# Supply_433Mhz.net
KiCad netlist of a schematic drawn in EAGLE
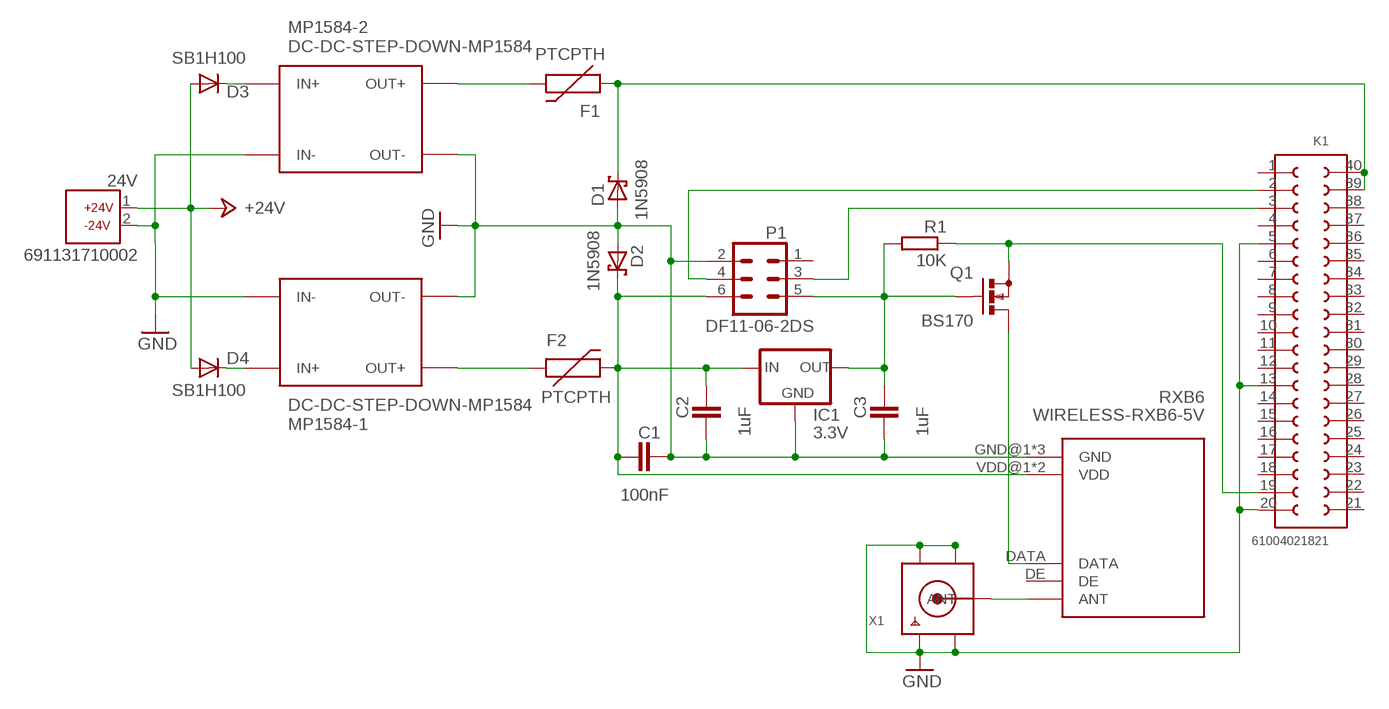
[diagram p0: schematic, sheet 1]

(export (version "E")
  (design (tool "Eeschema 10.0.6"))
  (components
    (comp (ref "24V")
      (value "691131710002")
      (footprint "eagle-import:691131710002")
      (libsource (lib "eagle-import") (part "691131710002"))
    )
    (comp (ref "C1")
      (value "100nF")
      (footprint "eagle-import:C2.5-3")
      (libsource (lib "eagle-import") (part "C2,5-3"))
    )
    (comp (ref "C2")
      (value "1uF")
      (footprint "eagle-import:C5B3")
      (libsource (lib "eagle-import") (part "C5/3"))
    )
    (comp (ref "C3")
      (value "1uF")
      (footprint "eagle-import:C5B3")
      (libsource (lib "eagle-import") (part "C5/3"))
    )
    (comp (ref "D1")
      (value "1N5908")
      (footprint "eagle-import:C4111-15")
      (libsource (lib "eagle-import") (part "1N5908"))
    )
    (comp (ref "D2")
      (value "1N5908")
      (footprint "eagle-import:C4111-15")
      (libsource (lib "eagle-import") (part "1N5908"))
    )
    (comp (ref "D3")
      (value "SB1H100")
      (footprint "eagle-import:DO41-7.6")
      (libsource (lib "eagle-import") (part "DIODE-DO41-7.6"))
    )
    (comp (ref "D4")
      (value "SB1H100")
      (footprint "eagle-import:DO41-7.6")
      (libsource (lib "eagle-import") (part "DIODE-DO41-7.6"))
    )
    (comp (ref "F1")
      (value "PTCPTH")
      (footprint "eagle-import:PTC")
      (libsource (lib "eagle-import") (part "PTCPTH"))
    )
    (comp (ref "F2")
      (value "PTCPTH")
      (footprint "eagle-import:PTC")
      (libsource (lib "eagle-import") (part "PTCPTH"))
    )
    (comp (ref "IC1")
      (value "3.3V")
      (footprint "eagle-import:TO92-INLINE")
      (libsource (lib "eagle-import") (part "MCP1700INLINE"))
    )
    (comp (ref "K1")
      (value "61004021821")
      (footprint "eagle-import:61004021821")
      (libsource (lib "eagle-import") (part "61004021821"))
    )
    (comp (ref "MP1584-1")
      (value "DC-DC-STEP-DOWN-MP1584")
      (footprint "eagle-import:DC-DC-STEP-DOWN-MP1584")
      (libsource (lib "eagle-import") (part "DC-DC-STEP-DOWN-MP1584"))
    )
    (comp (ref "MP1584-2")
      (value "DC-DC-STEP-DOWN-MP1584")
      (footprint "eagle-import:DC-DC-STEP-DOWN-MP1584")
      (libsource (lib "eagle-import") (part "DC-DC-STEP-DOWN-MP1584"))
    )
    (comp (ref "P1")
      (value "DF11-06-2DS")
      (footprint "eagle-import:DF11-06DP-2DS")
      (libsource (lib "eagle-import") (part "DF11-06-2DS"))
    )
    (comp (ref "Q1")
      (value "BS170")
      (footprint "eagle-import:SOT54E")
      (fields (field (name "MF") "ON SEMICONDUCTOR") (field (name "MPN") "BS170G"))
      (libsource (lib "eagle-import") (part "BS170"))
    )
    (comp (ref "R1")
      (value "10K")
      (footprint "eagle-import:0204V")
      (libsource (lib "eagle-import") (part "R-EU_0204/2V"))
    )
    (comp (ref "RXB6")
      (value "WIRELESS-RXB6-5V")
      (footprint "eagle-import:WIRELESS-RXB6-5V")
      (libsource (lib "eagle-import") (part "WIRELESS-RXB6-5V"))
    )
    (comp (ref "X1")
      (value "SMACONNECTOR")
      (footprint "eagle-import:SMA90_DIP")
      (libsource (lib "eagle-import") (part "SMACONNECTOR"))
    )
  )
  (nets
    (net (code "1") (name "+24V") (class "Default")
      (node (ref "24V") (pin "1") (pinfunction "1_1") (pintype "passive"))
      (node (ref "D3") (pin "A") (pinfunction "A_A") (pintype "passive"))
      (node (ref "D4") (pin "A") (pinfunction "A_A") (pintype "passive"))
    )
    (net (code "2") (name "GND") (class "Default")
      (node (ref "24V") (pin "2") (pinfunction "2_2") (pintype "passive"))
      (node (ref "C1") (pin "1") (pinfunction "1_1") (pintype "passive"))
      (node (ref "C2") (pin "2") (pinfunction "2_2") (pintype "passive"))
      (node (ref "C3") (pin "2") (pinfunction "2_2") (pintype "passive"))
      (node (ref "D1") (pin "A") (pinfunction "A_A") (pintype "passive"))
      (node (ref "D2") (pin "A") (pinfunction "A_A") (pintype "passive"))
      (node (ref "IC1") (pin "1") (pinfunction "GND_1") (pintype "input"))
      (node (ref "K1") (pin "13") (pinfunction "13_13") (pintype "passive"))
      (node (ref "K1") (pin "20") (pinfunction "20_20") (pintype "passive"))
      (node (ref "K1") (pin "5") (pinfunction "5_5") (pintype "passive"))
      (node (ref "MP1584-1") (pin "IN-0") (pinfunction "IN-_IN-0") (pintype "bidirectional"))
      (node (ref "MP1584-1") (pin "IN-1") (pinfunction "IN-_IN-1") (pintype "bidirectional"))
      (node (ref "MP1584-1") (pin "OUT-0") (pinfunction "OUT-_OUT-0") (pintype "bidirectional"))
      (node (ref "MP1584-1") (pin "OUT-1") (pinfunction "OUT-_OUT-1") (pintype "bidirectional"))
      (node (ref "MP1584-2") (pin "IN-0") (pinfunction "IN-_IN-0") (pintype "bidirectional"))
      (node (ref "MP1584-2") (pin "IN-1") (pinfunction "IN-_IN-1") (pintype "bidirectional"))
      (node (ref "MP1584-2") (pin "OUT-0") (pinfunction "OUT-_OUT-0") (pintype "bidirectional"))
      (node (ref "MP1584-2") (pin "OUT-1") (pinfunction "OUT-_OUT-1") (pintype "bidirectional"))
      (node (ref "P1") (pin "2") (pinfunction "2_2") (pintype "passive"))
      (node (ref "RXB6") (pin "GND@1") (pinfunction "GND_GND@1") (pintype "bidirectional"))
      (node (ref "RXB6") (pin "GND@2") (pinfunction "GND_GND@2") (pintype "bidirectional"))
      (node (ref "RXB6") (pin "GND@3") (pinfunction "GND_GND@3") (pintype "bidirectional"))
      (node (ref "X1") (pin "GND1") (pinfunction "GND1_GND1") (pintype "power_in"))
      (node (ref "X1") (pin "GND2") (pinfunction "GND2_GND2") (pintype "power_in"))
      (node (ref "X1") (pin "GND3") (pinfunction "GND3_GND3") (pintype "power_in"))
      (node (ref "X1") (pin "GND4") (pinfunction "GND4_GND4") (pintype "power_in"))
    )
    (net (code "3") (name "Net-(D3-PadC)") (class "Default")
      (node (ref "D3") (pin "C") (pinfunction "C_C") (pintype "passive"))
      (node (ref "MP1584-2") (pin "IN+0") (pinfunction "IN+_IN+0") (pintype "bidirectional"))
      (node (ref "MP1584-2") (pin "IN+1") (pinfunction "IN+_IN+1") (pintype "bidirectional"))
    )
    (net (code "4") (name "Net-(D4-PadC)") (class "Default")
      (node (ref "D4") (pin "C") (pinfunction "C_C") (pintype "passive"))
      (node (ref "MP1584-1") (pin "IN+0") (pinfunction "IN+_IN+0") (pintype "bidirectional"))
      (node (ref "MP1584-1") (pin "IN+1") (pinfunction "IN+_IN+1") (pintype "bidirectional"))
    )
    (net (code "5") (name "Net-(F1-1)") (class "Default")
      (node (ref "D1") (pin "C") (pinfunction "C_C") (pintype "passive"))
      (node (ref "F1") (pin "P$1") (pinfunction "1_P$1") (pintype "bidirectional"))
      (node (ref "K1") (pin "39") (pinfunction "39_39") (pintype "passive"))
      (node (ref "K1") (pin "40") (pinfunction "40_40") (pintype "passive"))
    )
    (net (code "6") (name "Net-(F1-2)") (class "Default")
      (node (ref "F1") (pin "P$2") (pinfunction "2_P$2") (pintype "bidirectional"))
      (node (ref "MP1584-2") (pin "OUT+0") (pinfunction "OUT+_OUT+0") (pintype "bidirectional"))
      (node (ref "MP1584-2") (pin "OUT+1") (pinfunction "OUT+_OUT+1") (pintype "bidirectional"))
    )
    (net (code "7") (name "Net-(F2-1)") (class "Default")
      (node (ref "F2") (pin "P$1") (pinfunction "1_P$1") (pintype "bidirectional"))
      (node (ref "MP1584-1") (pin "OUT+0") (pinfunction "OUT+_OUT+0") (pintype "bidirectional"))
      (node (ref "MP1584-1") (pin "OUT+1") (pinfunction "OUT+_OUT+1") (pintype "bidirectional"))
    )
    (net (code "8") (name "Net-(F2-2)") (class "Default")
      (node (ref "C1") (pin "2") (pinfunction "2_2") (pintype "passive"))
      (node (ref "C2") (pin "1") (pinfunction "1_1") (pintype "passive"))
      (node (ref "D2") (pin "C") (pinfunction "C_C") (pintype "passive"))
      (node (ref "F2") (pin "P$2") (pinfunction "2_P$2") (pintype "bidirectional"))
      (node (ref "IC1") (pin "2") (pinfunction "IN_2") (pintype "input"))
      (node (ref "P1") (pin "6") (pinfunction "6_6") (pintype "passive"))
      (node (ref "RXB6") (pin "VDD@1") (pinfunction "VDD_VDD@1") (pintype "bidirectional"))
      (node (ref "RXB6") (pin "VDD@2") (pinfunction "VDD_VDD@2") (pintype "bidirectional"))
    )
    (net (code "9") (name "Net-(IC1-OUT)") (class "Default")
      (node (ref "C3") (pin "1") (pinfunction "1_1") (pintype "passive"))
      (node (ref "IC1") (pin "3") (pinfunction "OUT_3") (pintype "passive"))
      (node (ref "P1") (pin "5") (pinfunction "5_5") (pintype "passive"))
      (node (ref "Q1") (pin "G") (pinfunction "G_G") (pintype "passive"))
      (node (ref "R1") (pin "2") (pinfunction "2_2") (pintype "passive"))
    )
    (net (code "10") (name "Net-(K1-Pad2)") (class "Default")
      (node (ref "K1") (pin "2") (pinfunction "2_2") (pintype "passive"))
      (node (ref "P1") (pin "4") (pinfunction "4_4") (pintype "passive"))
    )
    (net (code "11") (name "Net-(K1-Pad3)") (class "Default")
      (node (ref "K1") (pin "3") (pinfunction "3_3") (pintype "passive"))
      (node (ref "P1") (pin "3") (pinfunction "3_3") (pintype "passive"))
    )
    (net (code "12") (name "Net-(K1-Pad19)") (class "Default")
      (node (ref "K1") (pin "19") (pinfunction "19_19") (pintype "passive"))
      (node (ref "Q1") (pin "S") (pinfunction "S_S") (pintype "passive"))
      (node (ref "R1") (pin "1") (pinfunction "1_1") (pintype "passive"))
    )
    (net (code "13") (name "Net-(Q1-PadD)") (class "Default")
      (node (ref "Q1") (pin "D") (pinfunction "D_D") (pintype "passive"))
      (node (ref "RXB6") (pin "DATA") (pinfunction "DATA_DATA") (pintype "output"))
    )
    (net (code "14") (name "Net-(X1-ANT)") (class "Default")
      (node (ref "RXB6") (pin "ANT") (pinfunction "ANT_ANT") (pintype "input"))
      (node (ref "X1") (pin "ANTENNA") (pinfunction "ANT_ANTENNA") (pintype "bidirectional"))
    )
    (net (code "15") (name "unconnected-(K1-Pad1)") (class "Default")
      (node (ref "K1") (pin "1") (pinfunction "1_1") (pintype "passive"))
    )
    (net (code "16") (name "unconnected-(K1-Pad4)") (class "Default")
      (node (ref "K1") (pin "4") (pinfunction "4_4") (pintype "passive"))
    )
    (net (code "17") (name "unconnected-(K1-Pad6)") (class "Default")
      (node (ref "K1") (pin "6") (pinfunction "6_6") (pintype "passive"))
    )
    (net (code "18") (name "unconnected-(K1-Pad7)") (class "Default")
      (node (ref "K1") (pin "7") (pinfunction "7_7") (pintype "passive"))
    )
    (net (code "19") (name "unconnected-(K1-Pad8)") (class "Default")
      (node (ref "K1") (pin "8") (pinfunction "8_8") (pintype "passive"))
    )
    (net (code "20") (name "unconnected-(K1-Pad9)") (class "Default")
      (node (ref "K1") (pin "9") (pinfunction "9_9") (pintype "passive"))
    )
    (net (code "21") (name "unconnected-(K1-Pad10)") (class "Default")
      (node (ref "K1") (pin "10") (pinfunction "10_10") (pintype "passive"))
    )
    (net (code "22") (name "unconnected-(K1-Pad11)") (class "Default")
      (node (ref "K1") (pin "11") (pinfunction "11_11") (pintype "passive"))
    )
    (net (code "23") (name "unconnected-(K1-Pad12)") (class "Default")
      (node (ref "K1") (pin "12") (pinfunction "12_12") (pintype "passive"))
    )
    (net (code "24") (name "unconnected-(K1-Pad14)") (class "Default")
      (node (ref "K1") (pin "14") (pinfunction "14_14") (pintype "passive"))
    )
    (net (code "25") (name "unconnected-(K1-Pad15)") (class "Default")
      (node (ref "K1") (pin "15") (pinfunction "15_15") (pintype "passive"))
    )
    (net (code "26") (name "unconnected-(K1-Pad16)") (class "Default")
      (node (ref "K1") (pin "16") (pinfunction "16_16") (pintype "passive"))
    )
    (net (code "27") (name "unconnected-(K1-Pad17)") (class "Default")
      (node (ref "K1") (pin "17") (pinfunction "17_17") (pintype "passive"))
    )
    (net (code "28") (name "unconnected-(K1-Pad18)") (class "Default")
      (node (ref "K1") (pin "18") (pinfunction "18_18") (pintype "passive"))
    )
    (net (code "29") (name "unconnected-(K1-Pad21)") (class "Default")
      (node (ref "K1") (pin "21") (pinfunction "21_21") (pintype "passive"))
    )
    (net (code "30") (name "unconnected-(K1-Pad22)") (class "Default")
      (node (ref "K1") (pin "22") (pinfunction "22_22") (pintype "passive"))
    )
    (net (code "31") (name "unconnected-(K1-Pad23)") (class "Default")
      (node (ref "K1") (pin "23") (pinfunction "23_23") (pintype "passive"))
    )
    (net (code "32") (name "unconnected-(K1-Pad24)") (class "Default")
      (node (ref "K1") (pin "24") (pinfunction "24_24") (pintype "passive"))
    )
    (net (code "33") (name "unconnected-(K1-Pad25)") (class "Default")
      (node (ref "K1") (pin "25") (pinfunction "25_25") (pintype "passive"))
    )
    (net (code "34") (name "unconnected-(K1-Pad26)") (class "Default")
      (node (ref "K1") (pin "26") (pinfunction "26_26") (pintype "passive"))
    )
    (net (code "35") (name "unconnected-(K1-Pad27)") (class "Default")
      (node (ref "K1") (pin "27") (pinfunction "27_27") (pintype "passive"))
    )
    (net (code "36") (name "unconnected-(K1-Pad28)") (class "Default")
      (node (ref "K1") (pin "28") (pinfunction "28_28") (pintype "passive"))
    )
    (net (code "37") (name "unconnected-(K1-Pad29)") (class "Default")
      (node (ref "K1") (pin "29") (pinfunction "29_29") (pintype "passive"))
    )
    (net (code "38") (name "unconnected-(K1-Pad30)") (class "Default")
      (node (ref "K1") (pin "30") (pinfunction "30_30") (pintype "passive"))
    )
    (net (code "39") (name "unconnected-(K1-Pad31)") (class "Default")
      (node (ref "K1") (pin "31") (pinfunction "31_31") (pintype "passive"))
    )
    (net (code "40") (name "unconnected-(K1-Pad32)") (class "Default")
      (node (ref "K1") (pin "32") (pinfunction "32_32") (pintype "passive"))
    )
    (net (code "41") (name "unconnected-(K1-Pad33)") (class "Default")
      (node (ref "K1") (pin "33") (pinfunction "33_33") (pintype "passive"))
    )
    (net (code "42") (name "unconnected-(K1-Pad34)") (class "Default")
      (node (ref "K1") (pin "34") (pinfunction "34_34") (pintype "passive"))
    )
    (net (code "43") (name "unconnected-(K1-Pad35)") (class "Default")
      (node (ref "K1") (pin "35") (pinfunction "35_35") (pintype "passive"))
    )
    (net (code "44") (name "unconnected-(K1-Pad36)") (class "Default")
      (node (ref "K1") (pin "36") (pinfunction "36_36") (pintype "passive"))
    )
    (net (code "45") (name "unconnected-(K1-Pad37)") (class "Default")
      (node (ref "K1") (pin "37") (pinfunction "37_37") (pintype "passive"))
    )
    (net (code "46") (name "unconnected-(K1-Pad38)") (class "Default")
      (node (ref "K1") (pin "38") (pinfunction "38_38") (pintype "passive"))
    )
    (net (code "47") (name "unconnected-(P1-Pad1)") (class "Default")
      (node (ref "P1") (pin "1") (pinfunction "1_1") (pintype "passive"))
    )
    (net (code "48") (name "unconnected-(RXB6-PadDE)") (class "Default")
      (node (ref "RXB6") (pin "DE") (pinfunction "DE_DE") (pintype "output"))
    )
  )
)
